# implant8.net
KiCad netlist of a schematic drawn in EAGLE
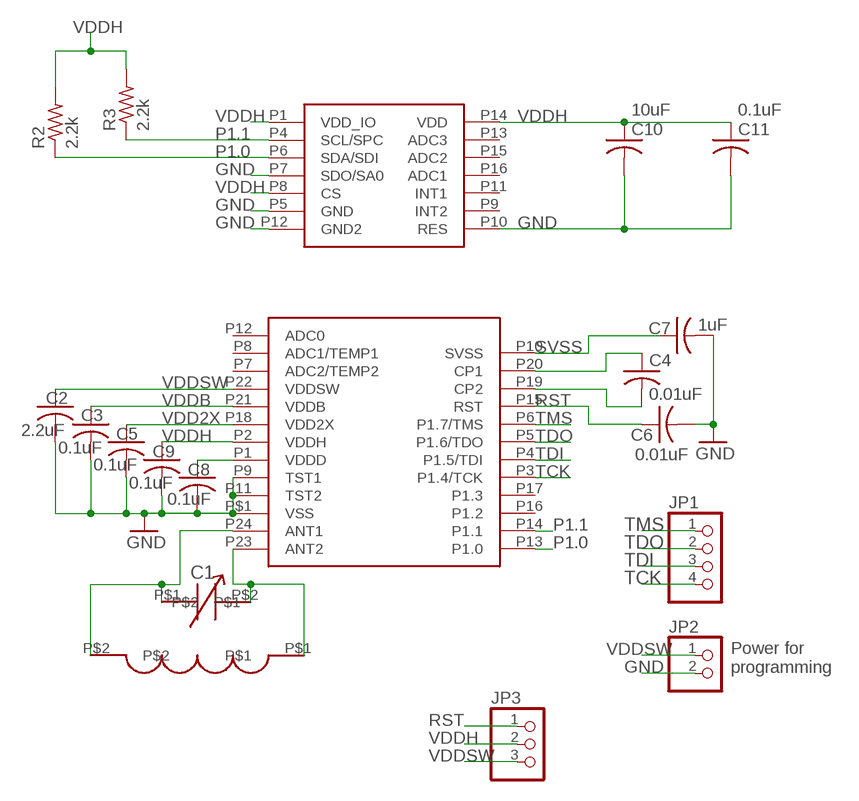
[diagram p0: schematic, sheet 1]

(export (version "E")
  (design (tool "Eeschema 10.0.6"))
  (components
    (comp (ref "C2")
      (value "2.2uF")
      (footprint "eagle-import:C0805")
      (libsource (lib "eagle-import") (part "C-USC0805"))
    )
    (comp (ref "C3")
      (value "0.1uF")
      (footprint "eagle-import:C0805")
      (libsource (lib "eagle-import") (part "C-USC0805"))
    )
    (comp (ref "C4")
      (value "0.01uF")
      (footprint "eagle-import:C0805")
      (libsource (lib "eagle-import") (part "C-USC0805"))
    )
    (comp (ref "C5")
      (value "0.1uF")
      (footprint "eagle-import:C0805")
      (libsource (lib "eagle-import") (part "C-USC0805"))
    )
    (comp (ref "C6")
      (value "0.01uF")
      (footprint "eagle-import:C0805")
      (libsource (lib "eagle-import") (part "C-USC0805"))
    )
    (comp (ref "C7")
      (value "1uF")
      (footprint "eagle-import:C0805")
      (libsource (lib "eagle-import") (part "C-USC0805"))
    )
    (comp (ref "C8")
      (value "0.1uF")
      (footprint "eagle-import:C0805")
      (libsource (lib "eagle-import") (part "C-USC0805"))
    )
    (comp (ref "C9")
      (value "0.1uF")
      (footprint "eagle-import:C0805")
      (libsource (lib "eagle-import") (part "C-USC0805"))
    )
    (comp (ref "C10")
      (value "10uF")
      (footprint "eagle-import:C0805")
      (libsource (lib "eagle-import") (part "C-USC0805"))
    )
    (comp (ref "C11")
      (value "0.1uF")
      (footprint "eagle-import:C0805")
      (libsource (lib "eagle-import") (part "C-USC0805"))
    )
    (comp (ref "JP1")
      (value "PINHD-1X4")
      (footprint "eagle-import:1X04")
      (libsource (lib "eagle-import") (part "PINHD-1X4"))
    )
    (comp (ref "JP2")
      (value "PINHD-1X2")
      (footprint "eagle-import:1X02")
      (libsource (lib "eagle-import") (part "PINHD-1X2"))
    )
    (comp (ref "JP3")
      (value "PINHD-1X3")
      (footprint "eagle-import:1X03")
      (libsource (lib "eagle-import") (part "PINHD-1X3"))
    )
    (comp (ref "R2")
      (value "2.2k")
      (footprint "eagle-import:R0805")
      (libsource (lib "eagle-import") (part "R-US_R0805"))
    )
    (comp (ref "R3")
      (value "2.2k")
      (footprint "eagle-import:R0805")
      (libsource (lib "eagle-import") (part "R-US_R0805"))
    )
    (comp (ref "U$1")
      (value "RF430FRL152H")
      (footprint "eagle-import:VQFN")
      (libsource (lib "eagle-import") (part "RF430FRL152H"))
    )
    (comp (ref "U$2")
      (value "COILCOIL3")
      (footprint "eagle-import:COIL3")
      (libsource (lib "eagle-import") (part "COILCOIL3"))
    )
    (comp (ref "U$3")
      (value "VAR_CAP")
      (footprint "eagle-import:VAR_CAP")
      (libsource (lib "eagle-import") (part "VAR_CAP"))
    )
    (comp (ref "U$4")
      (value "LIS3DH")
      (footprint "eagle-import:LGA-16")
      (libsource (lib "eagle-import") (part "LIS3DH"))
    )
  )
  (nets
    (net (code "1") (name "/P1.0") (class "Default")
      (node (ref "R2") (pin "1") (pinfunction "1_1") (pintype "passive"))
      (node (ref "U$1") (pin "P13") (pinfunction "P1.0_P13") (pintype "bidirectional"))
      (node (ref "U$4") (pin "P6") (pinfunction "SDA/SDI_P6") (pintype "bidirectional"))
    )
    (net (code "2") (name "/P1.1") (class "Default")
      (node (ref "R3") (pin "1") (pinfunction "1_1") (pintype "passive"))
      (node (ref "U$1") (pin "P14") (pinfunction "P1.1_P14") (pintype "bidirectional"))
      (node (ref "U$4") (pin "P4") (pinfunction "SCL/SPC_P4") (pintype "bidirectional"))
    )
    (net (code "3") (name "/RST") (class "Default")
      (node (ref "C6") (pin "1") (pinfunction "1_1") (pintype "passive"))
      (node (ref "JP3") (pin "1") (pinfunction "1_1") (pintype "passive"))
      (node (ref "U$1") (pin "P15") (pinfunction "RST_P15") (pintype "bidirectional"))
    )
    (net (code "4") (name "/SVSS") (class "Default")
      (node (ref "C7") (pin "1") (pinfunction "1_1") (pintype "passive"))
      (node (ref "U$1") (pin "P10") (pinfunction "SVSS_P10") (pintype "bidirectional"))
    )
    (net (code "5") (name "/TCK") (class "Default")
      (node (ref "JP1") (pin "4") (pinfunction "4_4") (pintype "passive"))
      (node (ref "U$1") (pin "P3") (pinfunction "P1.4/TCK_P3") (pintype "bidirectional"))
    )
    (net (code "6") (name "/TDI") (class "Default")
      (node (ref "JP1") (pin "3") (pinfunction "3_3") (pintype "passive"))
      (node (ref "U$1") (pin "P4") (pinfunction "P1.5/TDI_P4") (pintype "bidirectional"))
    )
    (net (code "7") (name "/TDO") (class "Default")
      (node (ref "JP1") (pin "2") (pinfunction "2_2") (pintype "passive"))
      (node (ref "U$1") (pin "P5") (pinfunction "P1.6/TDO_P5") (pintype "bidirectional"))
    )
    (net (code "8") (name "/TMS") (class "Default")
      (node (ref "JP1") (pin "1") (pinfunction "1_1") (pintype "passive"))
      (node (ref "U$1") (pin "P6") (pinfunction "P1.7/TMS_P6") (pintype "bidirectional"))
    )
    (net (code "9") (name "/VDD2X") (class "Default")
      (node (ref "C5") (pin "1") (pinfunction "1_1") (pintype "passive"))
      (node (ref "U$1") (pin "P18") (pinfunction "VDD2X_P18") (pintype "bidirectional"))
    )
    (net (code "10") (name "/VDDB") (class "Default")
      (node (ref "C3") (pin "1") (pinfunction "1_1") (pintype "passive"))
      (node (ref "U$1") (pin "P21") (pinfunction "VDDB_P21") (pintype "bidirectional"))
    )
    (net (code "11") (name "/VDDH") (class "Default")
      (node (ref "C10") (pin "1") (pinfunction "1_1") (pintype "passive"))
      (node (ref "C11") (pin "1") (pinfunction "1_1") (pintype "passive"))
      (node (ref "C9") (pin "1") (pinfunction "1_1") (pintype "passive"))
      (node (ref "JP3") (pin "2") (pinfunction "2_2") (pintype "passive"))
      (node (ref "R2") (pin "2") (pinfunction "2_2") (pintype "passive"))
      (node (ref "R3") (pin "2") (pinfunction "2_2") (pintype "passive"))
      (node (ref "U$1") (pin "P2") (pinfunction "VDDH_P2") (pintype "bidirectional"))
      (node (ref "U$4") (pin "P1") (pinfunction "VDD_IO_P1") (pintype "bidirectional"))
      (node (ref "U$4") (pin "P14") (pinfunction "VDD_P14") (pintype "bidirectional"))
      (node (ref "U$4") (pin "P8") (pinfunction "CS_P8") (pintype "bidirectional"))
    )
    (net (code "12") (name "/VDDSW") (class "Default")
      (node (ref "C2") (pin "1") (pinfunction "1_1") (pintype "passive"))
      (node (ref "JP2") (pin "1") (pinfunction "1_1") (pintype "passive"))
      (node (ref "JP3") (pin "3") (pinfunction "3_3") (pintype "passive"))
      (node (ref "U$1") (pin "P22") (pinfunction "VDDSW_P22") (pintype "bidirectional"))
    )
    (net (code "13") (name "GND") (class "Default")
      (node (ref "C10") (pin "2") (pinfunction "2_2") (pintype "passive"))
      (node (ref "C11") (pin "2") (pinfunction "2_2") (pintype "passive"))
      (node (ref "C2") (pin "2") (pinfunction "2_2") (pintype "passive"))
      (node (ref "C3") (pin "2") (pinfunction "2_2") (pintype "passive"))
      (node (ref "C5") (pin "2") (pinfunction "2_2") (pintype "passive"))
      (node (ref "C6") (pin "2") (pinfunction "2_2") (pintype "passive"))
      (node (ref "C7") (pin "2") (pinfunction "2_2") (pintype "passive"))
      (node (ref "C8") (pin "2") (pinfunction "2_2") (pintype "passive"))
      (node (ref "C9") (pin "2") (pinfunction "2_2") (pintype "passive"))
      (node (ref "JP2") (pin "2") (pinfunction "2_2") (pintype "passive"))
      (node (ref "U$1") (pin "P$1") (pinfunction "VSS_P$1") (pintype "bidirectional"))
      (node (ref "U$1") (pin "P11") (pinfunction "TST2_P11") (pintype "bidirectional"))
      (node (ref "U$1") (pin "P9") (pinfunction "TST1_P9") (pintype "bidirectional"))
      (node (ref "U$4") (pin "P10") (pinfunction "RES_P10") (pintype "bidirectional"))
      (node (ref "U$4") (pin "P12") (pinfunction "GND2_P12") (pintype "bidirectional"))
      (node (ref "U$4") (pin "P5") (pinfunction "GND_P5") (pintype "bidirectional"))
      (node (ref "U$4") (pin "P7") (pinfunction "SDO/SA0_P7") (pintype "bidirectional"))
    )
    (net (code "14") (name "Net-(U$1-ANT1)") (class "Default")
      (node (ref "U$1") (pin "P24") (pinfunction "ANT1_P24") (pintype "bidirectional"))
      (node (ref "U$2") (pin "P$2") (pinfunction "P$2_P$2") (pintype "bidirectional"))
      (node (ref "U$3") (pin "P$1") (pinfunction "P$1_P$1") (pintype "bidirectional"))
    )
    (net (code "15") (name "Net-(U$1-ANT2)") (class "Default")
      (node (ref "U$1") (pin "P23") (pinfunction "ANT2_P23") (pintype "bidirectional"))
      (node (ref "U$2") (pin "P$1") (pinfunction "P$1_P$1") (pintype "bidirectional"))
      (node (ref "U$3") (pin "P$2") (pinfunction "P$2_P$2") (pintype "bidirectional"))
    )
    (net (code "16") (name "Net-(U$1-CP1)") (class "Default")
      (node (ref "C4") (pin "1") (pinfunction "1_1") (pintype "passive"))
      (node (ref "U$1") (pin "P20") (pinfunction "CP1_P20") (pintype "bidirectional"))
    )
    (net (code "17") (name "Net-(U$1-CP2)") (class "Default")
      (node (ref "C4") (pin "2") (pinfunction "2_2") (pintype "passive"))
      (node (ref "U$1") (pin "P19") (pinfunction "CP2_P19") (pintype "bidirectional"))
    )
    (net (code "18") (name "Net-(U$1-VDDD)") (class "Default")
      (node (ref "C8") (pin "1") (pinfunction "1_1") (pintype "passive"))
      (node (ref "U$1") (pin "P1") (pinfunction "VDDD_P1") (pintype "bidirectional"))
    )
    (net (code "19") (name "unconnected-(U$1-ADC0-PadP12)") (class "Default")
      (node (ref "U$1") (pin "P12") (pinfunction "ADC0_P12") (pintype "bidirectional"))
    )
    (net (code "20") (name "unconnected-(U$1-ADC1{slash}TEMP1-PadP8)") (class "Default")
      (node (ref "U$1") (pin "P8") (pinfunction "ADC1/TEMP1_P8") (pintype "bidirectional"))
    )
    (net (code "21") (name "unconnected-(U$1-ADC2{slash}TEMP2-PadP7)") (class "Default")
      (node (ref "U$1") (pin "P7") (pinfunction "ADC2/TEMP2_P7") (pintype "bidirectional"))
    )
    (net (code "22") (name "unconnected-(U$1-P1.2-PadP16)") (class "Default")
      (node (ref "U$1") (pin "P16") (pinfunction "P1.2_P16") (pintype "bidirectional"))
    )
    (net (code "23") (name "unconnected-(U$1-P1.3-PadP17)") (class "Default")
      (node (ref "U$1") (pin "P17") (pinfunction "P1.3_P17") (pintype "bidirectional"))
    )
    (net (code "24") (name "unconnected-(U$4-ADC1-PadP16)") (class "Default")
      (node (ref "U$4") (pin "P16") (pinfunction "ADC1_P16") (pintype "bidirectional"))
    )
    (net (code "25") (name "unconnected-(U$4-ADC2-PadP15)") (class "Default")
      (node (ref "U$4") (pin "P15") (pinfunction "ADC2_P15") (pintype "bidirectional"))
    )
    (net (code "26") (name "unconnected-(U$4-ADC3-PadP13)") (class "Default")
      (node (ref "U$4") (pin "P13") (pinfunction "ADC3_P13") (pintype "bidirectional"))
    )
    (net (code "27") (name "unconnected-(U$4-INT1-PadP11)") (class "Default")
      (node (ref "U$4") (pin "P11") (pinfunction "INT1_P11") (pintype "bidirectional"))
    )
    (net (code "28") (name "unconnected-(U$4-INT2-PadP9)") (class "Default")
      (node (ref "U$4") (pin "P9") (pinfunction "INT2_P9") (pintype "bidirectional"))
    )
  )
)
